# tiny-robot.net
KiCad netlist of a schematic drawn in EAGLE
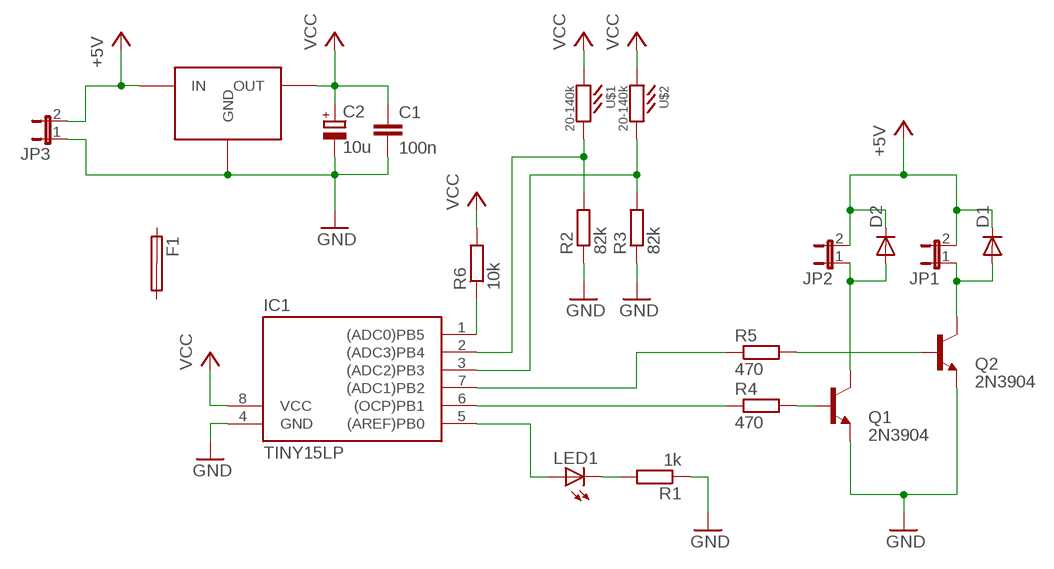
[diagram p0: schematic, sheet 1]

(export (version "E")
  (design (tool "Eeschema 10.0.6"))
  (components
    (comp (ref "C1")
      (value "100n")
      (footprint "eagle-import:C025-025X050")
      (libsource (lib "eagle-import") (part "C-EU025-025X050"))
    )
    (comp (ref "C2")
      (value "10u")
      (footprint "eagle-import:E2,5-6E")
      (libsource (lib "eagle-import") (part "CPOL-EUE2,5-6E"))
    )
    (comp (ref "D1")
      (value "1N4148DO35-7")
      (footprint "eagle-import:DO35-7")
      (libsource (lib "eagle-import") (part "1N4148DO35-7"))
    )
    (comp (ref "D2")
      (value "1N4148DO35-7")
      (footprint "eagle-import:DO35-7")
      (libsource (lib "eagle-import") (part "1N4148DO35-7"))
    )
    (comp (ref "F1")
      (value "SHK20L")
      (footprint "eagle-import:SHK20L")
      (libsource (lib "eagle-import") (part "SHK20L"))
    )
    (comp (ref "IC1")
      (value "TINY15LP")
      (footprint "eagle-import:DIL08")
      (libsource (lib "eagle-import") (part "TINY15LP"))
    )
    (comp (ref "JP1")
      (value "JP1E")
      (footprint "eagle-import:JP1")
      (libsource (lib "eagle-import") (part "JP1E"))
    )
    (comp (ref "JP2")
      (value "JP1E")
      (footprint "eagle-import:JP1")
      (libsource (lib "eagle-import") (part "JP1E"))
    )
    (comp (ref "JP3")
      (value "JP1E")
      (footprint "eagle-import:JP1")
      (libsource (lib "eagle-import") (part "JP1E"))
    )
    (comp (ref "LED1")
      (value "LED3MM")
      (footprint "eagle-import:LED3MM")
      (libsource (lib "eagle-import") (part "LED3MM"))
    )
    (comp (ref "Q1")
      (value "2N3904")
      (footprint "eagle-import:TO92")
      (libsource (lib "eagle-import") (part "2N3904"))
    )
    (comp (ref "Q2")
      (value "2N3904")
      (footprint "eagle-import:TO92")
      (libsource (lib "eagle-import") (part "2N3904"))
    )
    (comp (ref "R1")
      (value "1k")
      (footprint "eagle-import:0207_2V")
      (libsource (lib "eagle-import") (part "R-EU_0207/2V"))
    )
    (comp (ref "R2")
      (value "82k")
      (footprint "eagle-import:0207_5V")
      (libsource (lib "eagle-import") (part "R-EU_0207/5V"))
    )
    (comp (ref "R3")
      (value "82k")
      (footprint "eagle-import:0207_5V")
      (libsource (lib "eagle-import") (part "R-EU_0207/5V"))
    )
    (comp (ref "R4")
      (value "470")
      (footprint "eagle-import:0207_2V")
      (libsource (lib "eagle-import") (part "R-EU_0207/2V"))
    )
    (comp (ref "R5")
      (value "470")
      (footprint "eagle-import:0207_5V")
      (libsource (lib "eagle-import") (part "R-EU_0207/5V"))
    )
    (comp (ref "R6")
      (value "10k")
      (footprint "eagle-import:0207_5V")
      (libsource (lib "eagle-import") (part "R-EU_0207/5V"))
    )
    (comp (ref "U$1")
      (value "20-140k")
      (footprint "eagle-import:LDR-906014")
      (libsource (lib "eagle-import") (part "LDR-906014"))
    )
    (comp (ref "U$2")
      (value "20-140k")
      (footprint "eagle-import:LDR-906014")
      (libsource (lib "eagle-import") (part "LDR-906014"))
    )
    (comp (ref "U$3")
      (value "MCP1700")
      (footprint "eagle-import:TO92")
      (libsource (lib "eagle-import") (part "MCP1700"))
    )
  )
  (nets
    (net (code "1") (name "+5V") (class "Default")
      (node (ref "D1") (pin "C") (pinfunction "C_C") (pintype "passive"))
      (node (ref "D2") (pin "C") (pinfunction "C_C") (pintype "passive"))
      (node (ref "JP1") (pin "2") (pinfunction "2_2") (pintype "passive"))
      (node (ref "JP2") (pin "2") (pinfunction "2_2") (pintype "passive"))
      (node (ref "JP3") (pin "2") (pinfunction "2_2") (pintype "passive"))
      (node (ref "U$3") (pin "2") (pinfunction "IN_2") (pintype "bidirectional"))
    )
    (net (code "2") (name "GND") (class "Default")
      (node (ref "C1") (pin "2") (pinfunction "2_2") (pintype "passive"))
      (node (ref "C2") (pin "-") (pinfunction "-_-") (pintype "passive"))
      (node (ref "IC1") (pin "4") (pinfunction "GND_4") (pintype "power_in"))
      (node (ref "JP3") (pin "1") (pinfunction "1_1") (pintype "passive"))
      (node (ref "Q1") (pin "3") (pinfunction "E_3") (pintype "passive"))
      (node (ref "Q2") (pin "3") (pinfunction "E_3") (pintype "passive"))
      (node (ref "R1") (pin "1") (pinfunction "1_1") (pintype "passive"))
      (node (ref "R2") (pin "1") (pinfunction "1_1") (pintype "passive"))
      (node (ref "R3") (pin "1") (pinfunction "1_1") (pintype "passive"))
      (node (ref "U$3") (pin "3") (pinfunction "GND_3") (pintype "bidirectional"))
    )
    (net (code "3") (name "Net-(IC1-(ADC0)PB5)") (class "Default")
      (node (ref "IC1") (pin "1") (pinfunction "(ADC0)PB5_1") (pintype "bidirectional"))
      (node (ref "R6") (pin "1") (pinfunction "1_1") (pintype "passive"))
    )
    (net (code "4") (name "Net-(IC1-(ADC1)PB2)") (class "Default")
      (node (ref "IC1") (pin "7") (pinfunction "(ADC1)PB2_7") (pintype "bidirectional"))
      (node (ref "R5") (pin "1") (pinfunction "1_1") (pintype "passive"))
    )
    (net (code "5") (name "Net-(IC1-(ADC2)PB3)") (class "Default")
      (node (ref "IC1") (pin "3") (pinfunction "(ADC2)PB3_3") (pintype "bidirectional"))
      (node (ref "R3") (pin "2") (pinfunction "2_2") (pintype "passive"))
      (node (ref "U$2") (pin "P$2") (pinfunction "P$2_P$2") (pintype "passive"))
    )
    (net (code "6") (name "Net-(IC1-(ADC3)PB4)") (class "Default")
      (node (ref "IC1") (pin "2") (pinfunction "(ADC3)PB4_2") (pintype "bidirectional"))
      (node (ref "R2") (pin "2") (pinfunction "2_2") (pintype "passive"))
      (node (ref "U$1") (pin "P$2") (pinfunction "P$2_P$2") (pintype "passive"))
    )
    (net (code "7") (name "Net-(IC1-(AREF)PB0)") (class "Default")
      (node (ref "IC1") (pin "5") (pinfunction "(AREF)PB0_5") (pintype "bidirectional"))
      (node (ref "LED1") (pin "A") (pinfunction "A_A") (pintype "passive"))
    )
    (net (code "8") (name "Net-(IC1-(OCP)PB1)") (class "Default")
      (node (ref "IC1") (pin "6") (pinfunction "(OCP)PB1_6") (pintype "bidirectional"))
      (node (ref "R4") (pin "1") (pinfunction "1_1") (pintype "passive"))
    )
    (net (code "9") (name "Net-(LED1-C)") (class "Default")
      (node (ref "LED1") (pin "K") (pinfunction "C_K") (pintype "passive"))
      (node (ref "R1") (pin "2") (pinfunction "2_2") (pintype "passive"))
    )
    (net (code "10") (name "Net-(Q1-B)") (class "Default")
      (node (ref "Q1") (pin "2") (pinfunction "B_2") (pintype "passive"))
      (node (ref "R4") (pin "2") (pinfunction "2_2") (pintype "passive"))
    )
    (net (code "11") (name "Net-(Q1-C)") (class "Default")
      (node (ref "D2") (pin "A") (pinfunction "A_A") (pintype "passive"))
      (node (ref "JP2") (pin "1") (pinfunction "1_1") (pintype "passive"))
      (node (ref "Q1") (pin "1") (pinfunction "C_1") (pintype "passive"))
    )
    (net (code "12") (name "Net-(Q2-B)") (class "Default")
      (node (ref "Q2") (pin "2") (pinfunction "B_2") (pintype "passive"))
      (node (ref "R5") (pin "2") (pinfunction "2_2") (pintype "passive"))
    )
    (net (code "13") (name "Net-(Q2-C)") (class "Default")
      (node (ref "D1") (pin "A") (pinfunction "A_A") (pintype "passive"))
      (node (ref "JP1") (pin "1") (pinfunction "1_1") (pintype "passive"))
      (node (ref "Q2") (pin "1") (pinfunction "C_1") (pintype "passive"))
    )
    (net (code "14") (name "VCC") (class "Default")
      (node (ref "C1") (pin "1") (pinfunction "1_1") (pintype "passive"))
      (node (ref "C2") (pin "+") (pinfunction "+_+") (pintype "passive"))
      (node (ref "IC1") (pin "8") (pinfunction "VCC_8") (pintype "power_in"))
      (node (ref "R6") (pin "2") (pinfunction "2_2") (pintype "passive"))
      (node (ref "U$1") (pin "P$1") (pinfunction "P$1_P$1") (pintype "passive"))
      (node (ref "U$2") (pin "P$1") (pinfunction "P$1_P$1") (pintype "passive"))
      (node (ref "U$3") (pin "1") (pinfunction "OUT_1") (pintype "bidirectional"))
    )
    (net (code "15") (name "unconnected-(F1-Pad1A)") (class "Default")
      (node (ref "F1") (pin "1A") (pinfunction "1A_1A") (pintype "passive"))
    )
    (net (code "16") (name "unconnected-(F1-Pad1B)") (class "Default")
      (node (ref "F1") (pin "1B") (pinfunction "1B_1B") (pintype "passive"))
    )
    (net (code "17") (name "unconnected-(F1-Pad2A)") (class "Default")
      (node (ref "F1") (pin "2A") (pinfunction "2A_2A") (pintype "passive"))
    )
    (net (code "18") (name "unconnected-(F1-Pad2B)") (class "Default")
      (node (ref "F1") (pin "2B") (pinfunction "2B_2B") (pintype "passive"))
    )
  )
)
